# badge2.net
KiCad netlist of a schematic drawn in EAGLE
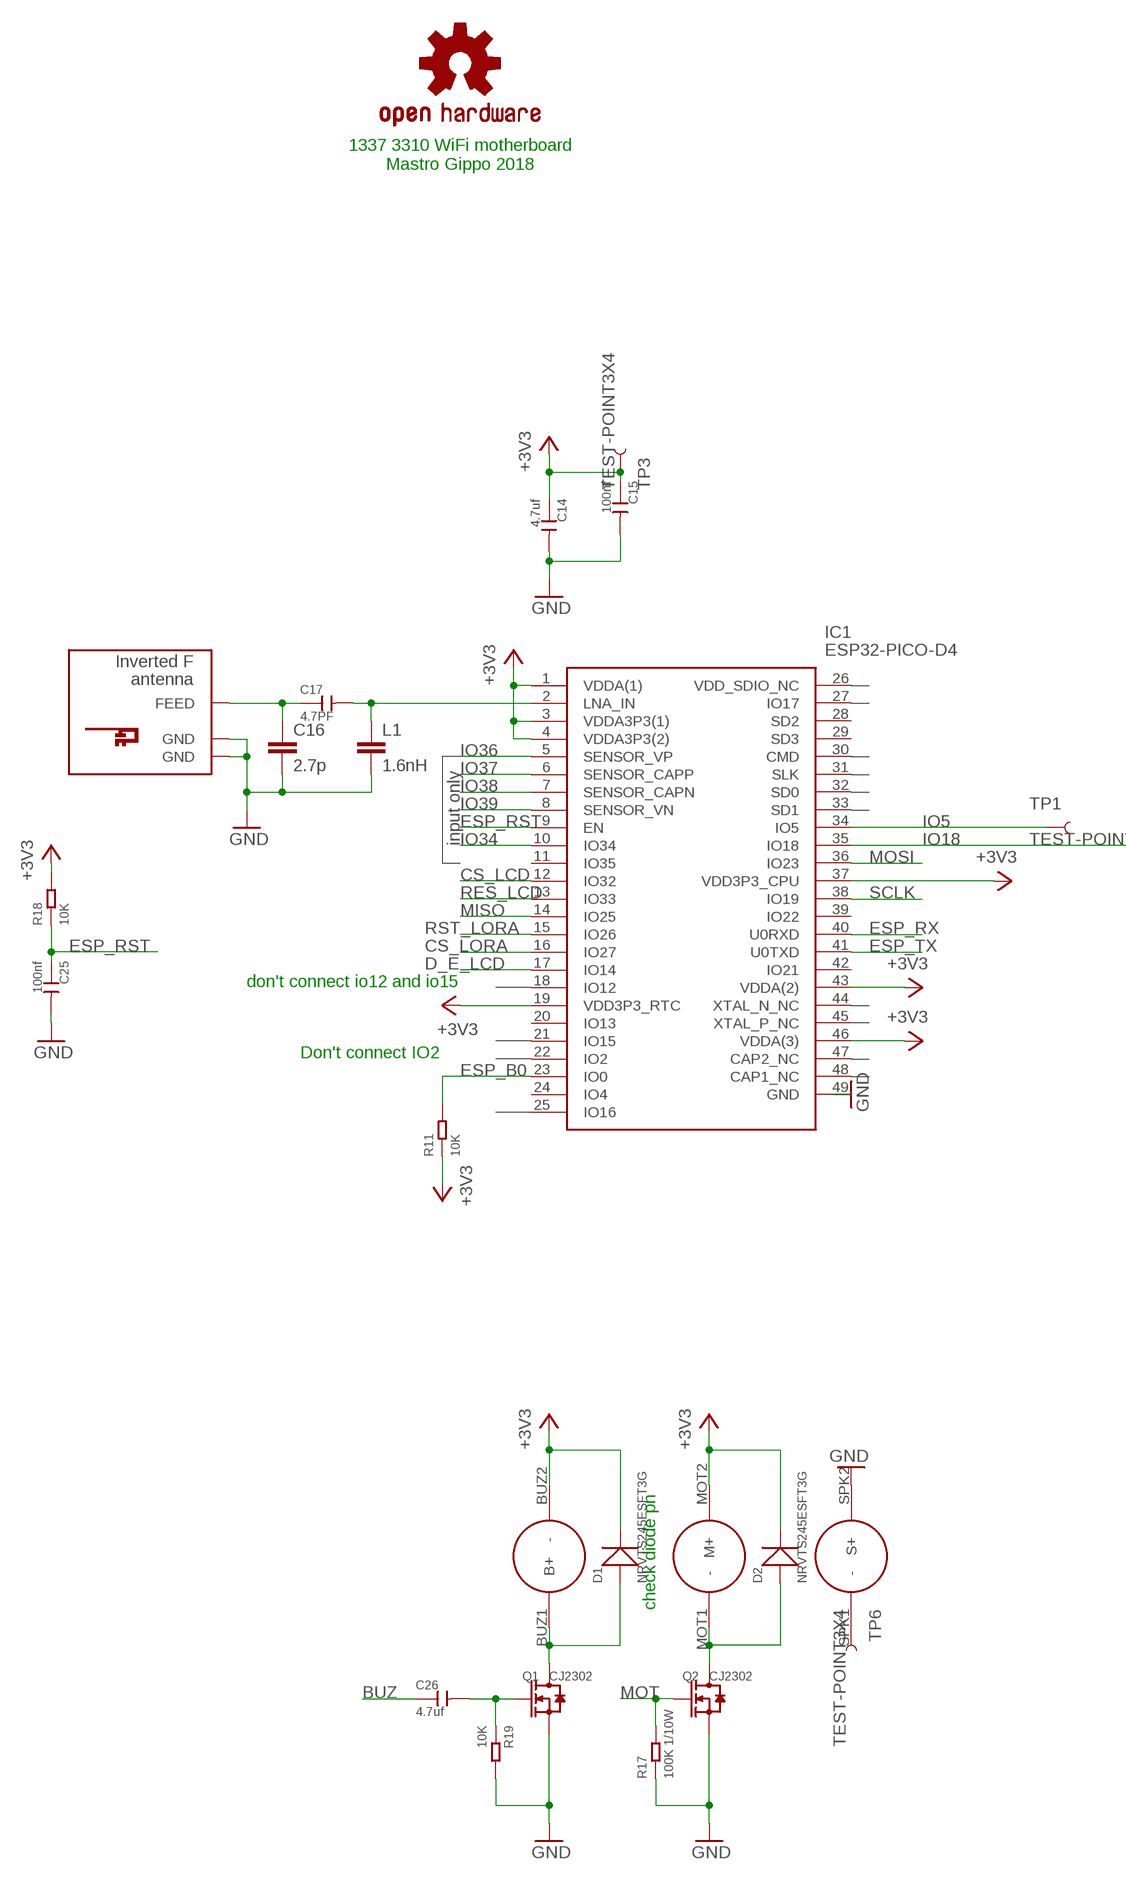
[diagram p0: schematic, sheet 1, part 1 of 2]
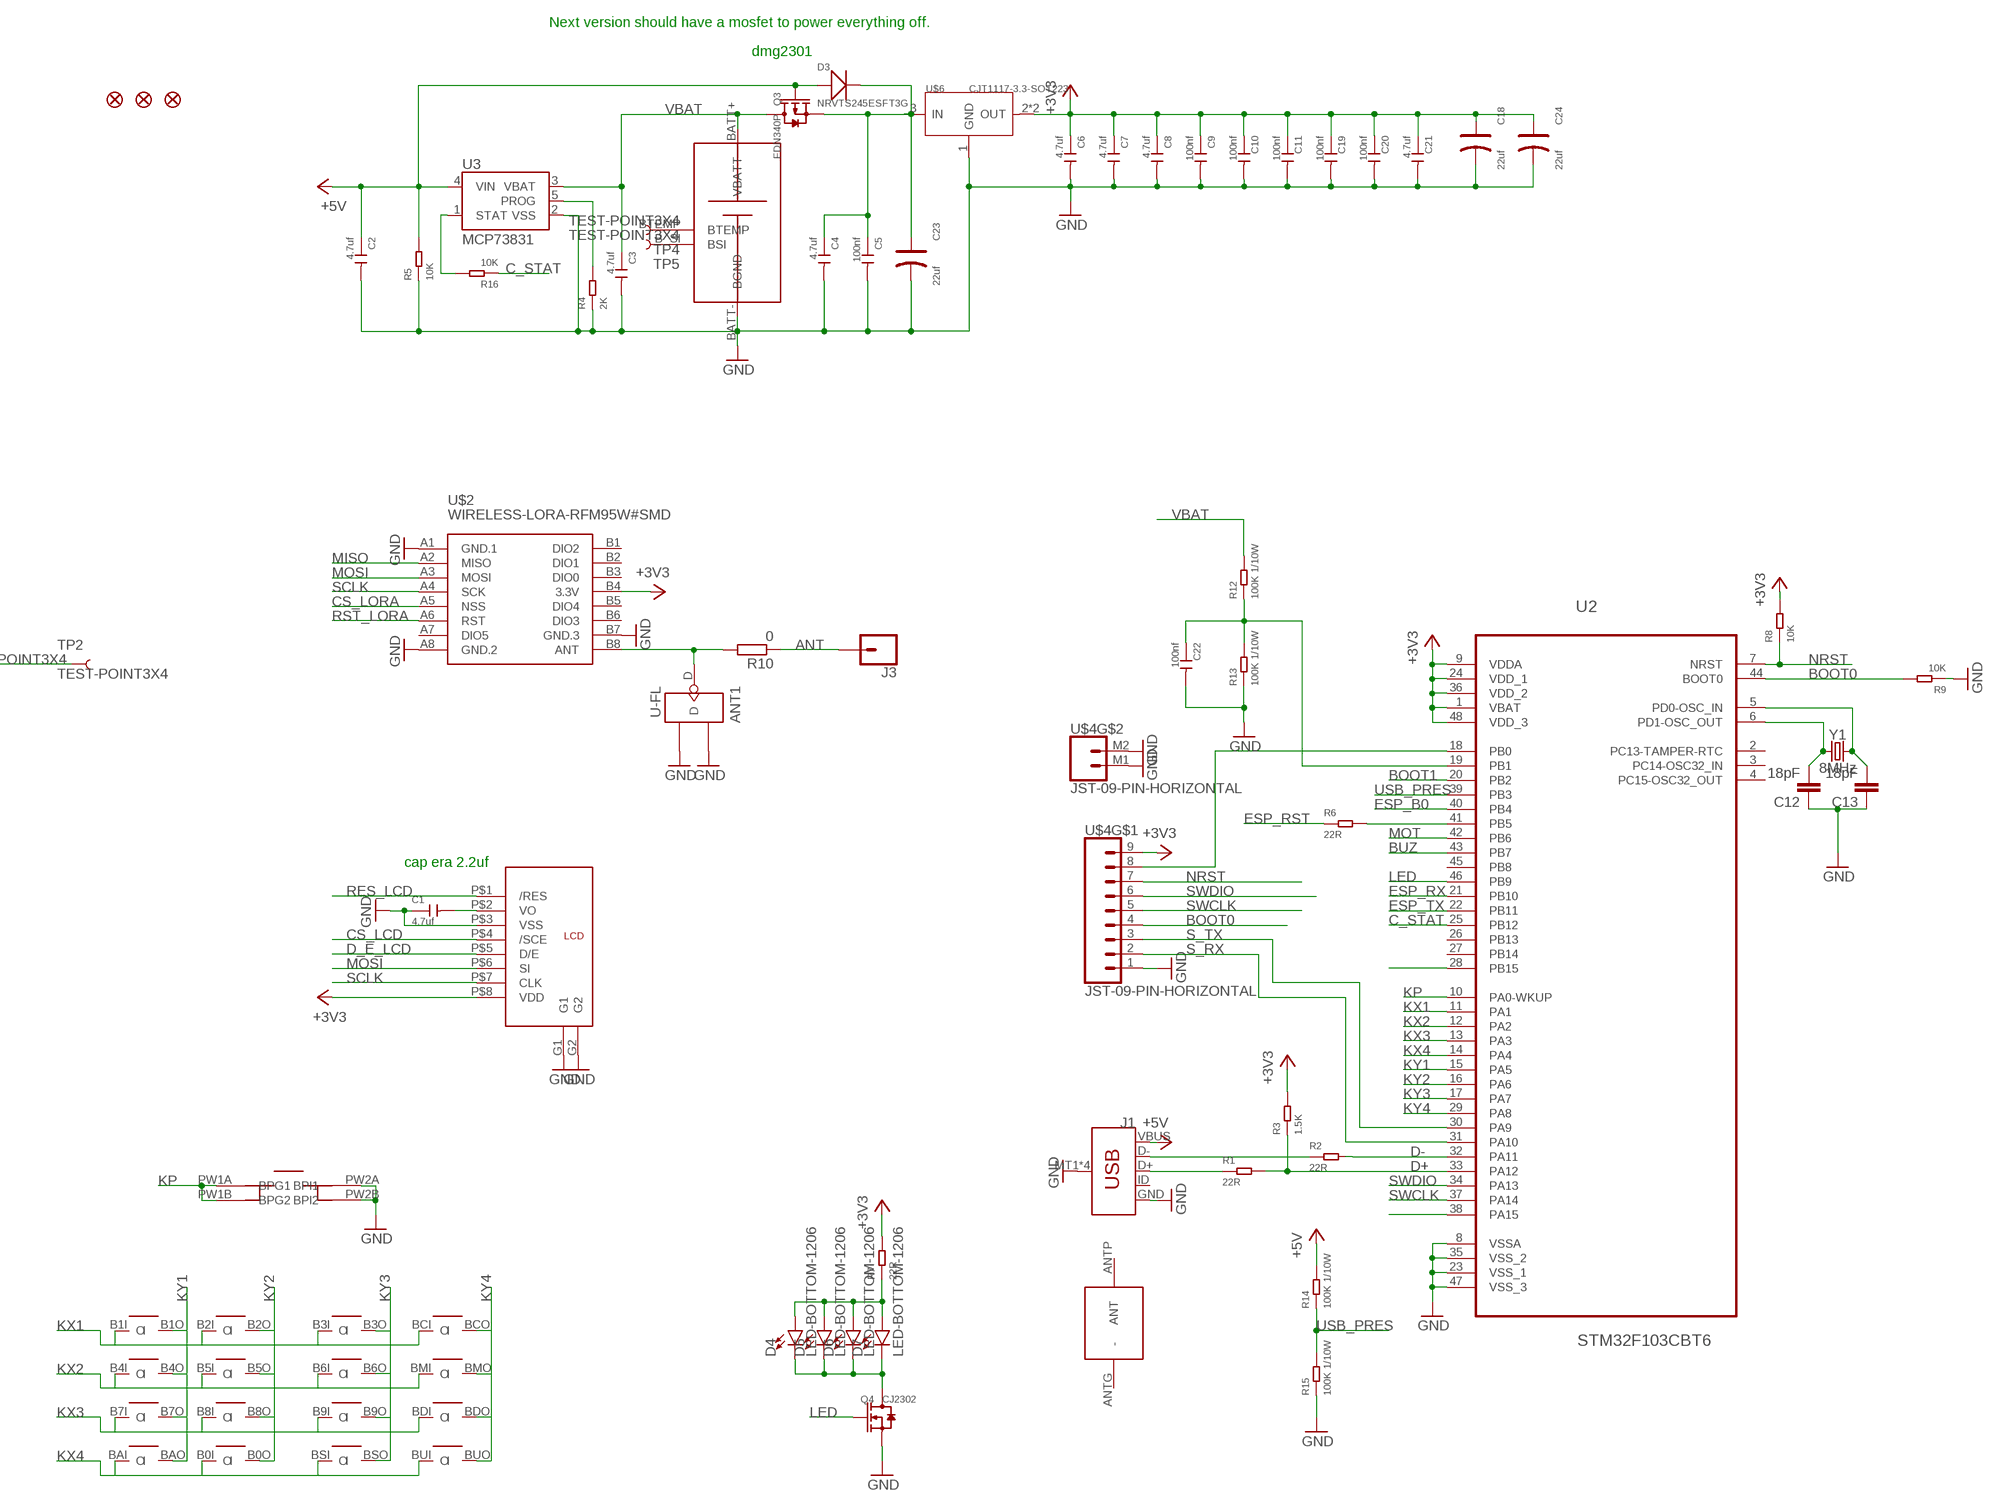
[diagram p1: schematic, sheet 1, part 2 of 2]

(export (version "E")
  (design (tool "Eeschema 10.0.6"))
  (components
    (comp (ref "ANT1")
      (value "U-FL")
      (footprint "eagle-import:U-FL3P-SMD-2.6X2.6X1.0MM")
      (libsource (lib "eagle-import") (part "ANTENNA-CONN-U-FL(3P)"))
    )
    (comp (ref "C1")
      (value "4.7uf")
      (footprint "eagle-import:C0603")
      (fields (field (name "MPN") "CC0603KRX5R6BB475"))
      (libsource (lib "eagle-import") (part "CERAMIC-4.7UF-10V-10%-X5R(0603)"))
    )
    (comp (ref "C2")
      (value "4.7uf")
      (footprint "eagle-import:C0603")
      (fields (field (name "MPN") "CC0603KRX5R6BB475"))
      (libsource (lib "eagle-import") (part "CERAMIC-4.7UF-10V-10%-X5R(0603)"))
    )
    (comp (ref "C3")
      (value "4.7uf")
      (footprint "eagle-import:C0603")
      (fields (field (name "MPN") "CC0603KRX5R6BB475"))
      (libsource (lib "eagle-import") (part "CERAMIC-4.7UF-10V-10%-X5R(0603)"))
    )
    (comp (ref "C4")
      (value "4.7uf")
      (footprint "eagle-import:C0603")
      (fields (field (name "MPN") "CC0603KRX5R6BB475"))
      (libsource (lib "eagle-import") (part "CERAMIC-4.7UF-10V-10%-X5R(0603)"))
    )
    (comp (ref "C5")
      (value "100nf")
      (footprint "eagle-import:C0603")
      (fields (field (name "MPN") "CC0603KRX7R9BB104"))
      (libsource (lib "eagle-import") (part "CERAMIC-100NF-50V-10%-X7R(0603)"))
    )
    (comp (ref "C6")
      (value "4.7uf")
      (footprint "eagle-import:C0603")
      (fields (field (name "MPN") "CC0603KRX5R6BB475"))
      (libsource (lib "eagle-import") (part "CERAMIC-4.7UF-10V-10%-X5R(0603)"))
    )
    (comp (ref "C7")
      (value "4.7uf")
      (footprint "eagle-import:C0603")
      (fields (field (name "MPN") "CC0603KRX5R6BB475"))
      (libsource (lib "eagle-import") (part "CERAMIC-4.7UF-10V-10%-X5R(0603)"))
    )
    (comp (ref "C8")
      (value "4.7uf")
      (footprint "eagle-import:C0603")
      (fields (field (name "MPN") "CC0603KRX5R6BB475"))
      (libsource (lib "eagle-import") (part "CERAMIC-4.7UF-10V-10%-X5R(0603)"))
    )
    (comp (ref "C9")
      (value "100nf")
      (footprint "eagle-import:C0603")
      (fields (field (name "MPN") "CC0603KRX7R9BB104"))
      (libsource (lib "eagle-import") (part "CERAMIC-100NF-50V-10%-X7R(0603)"))
    )
    (comp (ref "C10")
      (value "100nf")
      (footprint "eagle-import:C0603")
      (fields (field (name "MPN") "CC0603KRX7R9BB104"))
      (libsource (lib "eagle-import") (part "CERAMIC-100NF-50V-10%-X7R(0603)"))
    )
    (comp (ref "C11")
      (value "100nf")
      (footprint "eagle-import:C0603")
      (fields (field (name "MPN") "CC0603KRX7R9BB104"))
      (libsource (lib "eagle-import") (part "CERAMIC-100NF-50V-10%-X7R(0603)"))
    )
    (comp (ref "C12")
      (value "18pF")
      (footprint "eagle-import:0603")
      (libsource (lib "eagle-import") (part "18PF-0603-50V-5%"))
    )
    (comp (ref "C13")
      (value "18pF")
      (footprint "eagle-import:0603")
      (libsource (lib "eagle-import") (part "18PF-0603-50V-5%"))
    )
    (comp (ref "C14")
      (value "4.7uf")
      (footprint "eagle-import:C0603")
      (fields (field (name "MPN") "CC0603KRX5R6BB475"))
      (libsource (lib "eagle-import") (part "CERAMIC-4.7UF-10V-10%-X5R(0603)"))
    )
    (comp (ref "C15")
      (value "100nf")
      (footprint "eagle-import:C0603")
      (fields (field (name "MPN") "CC0603KRX7R9BB104"))
      (libsource (lib "eagle-import") (part "CERAMIC-100NF-50V-10%-X7R(0603)"))
    )
    (comp (ref "C16")
      (value "2.7p")
      (footprint "eagle-import:C0603")
      (libsource (lib "eagle-import") (part "C-EUC0603"))
    )
    (comp (ref "C17")
      (value "4.7PF")
      (footprint "eagle-import:C0603")
      (fields (field (name "MPN") "CC0603CRNPO9BN4R7"))
      (libsource (lib "eagle-import") (part "CERAMIC-4.7PF-50V-0.25PF-NPO(0603)"))
    )
    (comp (ref "C18")
      (value "22uf")
      (footprint "eagle-import:AVX-B")
      (fields (field (name "MPN") "TAJB226*016#NJ"))
      (libsource (lib "eagle-import") (part "TANTALUM-SMD-22UF-16V(AVX-B)"))
    )
    (comp (ref "C19")
      (value "100nf")
      (footprint "eagle-import:C0603")
      (fields (field (name "MPN") "CC0603KRX7R9BB104"))
      (libsource (lib "eagle-import") (part "CERAMIC-100NF-50V-10%-X7R(0603)"))
    )
    (comp (ref "C20")
      (value "100nf")
      (footprint "eagle-import:C0603")
      (fields (field (name "MPN") "CC0603KRX7R9BB104"))
      (libsource (lib "eagle-import") (part "CERAMIC-100NF-50V-10%-X7R(0603)"))
    )
    (comp (ref "C21")
      (value "4.7uf")
      (footprint "eagle-import:C0603")
      (fields (field (name "MPN") "CC0603KRX5R6BB475"))
      (libsource (lib "eagle-import") (part "CERAMIC-4.7UF-10V-10%-X5R(0603)"))
    )
    (comp (ref "C22")
      (value "100nf")
      (footprint "eagle-import:C0603")
      (fields (field (name "MPN") "CC0603KRX7R9BB104"))
      (libsource (lib "eagle-import") (part "CERAMIC-100NF-50V-10%-X7R(0603)"))
    )
    (comp (ref "C23")
      (value "22uf")
      (footprint "eagle-import:AVX-B")
      (fields (field (name "MPN") "TAJB226*016#NJ"))
      (libsource (lib "eagle-import") (part "TANTALUM-SMD-22UF-16V(AVX-B)"))
    )
    (comp (ref "C24")
      (value "22uf")
      (footprint "eagle-import:AVX-B")
      (fields (field (name "MPN") "TAJB226*016#NJ"))
      (libsource (lib "eagle-import") (part "TANTALUM-SMD-22UF-16V(AVX-B)"))
    )
    (comp (ref "C25")
      (value "100nf")
      (footprint "eagle-import:C0603")
      (fields (field (name "MPN") "CC0603KRX7R9BB104"))
      (libsource (lib "eagle-import") (part "CERAMIC-100NF-50V-10%-X7R(0603)"))
    )
    (comp (ref "C26")
      (value "4.7uf")
      (footprint "eagle-import:C0603")
      (fields (field (name "MPN") "CC0603KRX5R6BB475"))
      (libsource (lib "eagle-import") (part "CERAMIC-4.7UF-10V-10%-X5R(0603)"))
    )
    (comp (ref "D1")
      (value "NRVTS245ESFT3G")
      (footprint "eagle-import:SOD-123")
      (fields (field (name "MPN") "B5819W"))
      (libsource (lib "eagle-import") (part "SMD-DIODE-SCHOTTKY-20V-1A(SOD-123)"))
    )
    (comp (ref "D2")
      (value "NRVTS245ESFT3G")
      (footprint "eagle-import:SOD-123")
      (fields (field (name "MPN") "B5819W"))
      (libsource (lib "eagle-import") (part "SMD-DIODE-SCHOTTKY-20V-1A(SOD-123)"))
    )
    (comp (ref "D3")
      (value "NRVTS245ESFT3G")
      (footprint "eagle-import:SOD-123")
      (fields (field (name "MPN") "B5819W"))
      (libsource (lib "eagle-import") (part "SMD-DIODE-SCHOTTKY-20V-1A(SOD-123)"))
    )
    (comp (ref "D4")
      (value "LED-BOTTOM-1206")
      (footprint "eagle-import:LED-1206")
      (libsource (lib "eagle-import") (part "LED-BOTTOM-1206"))
    )
    (comp (ref "D5")
      (value "LED-BOTTOM-1206")
      (footprint "eagle-import:LED-1206")
      (libsource (lib "eagle-import") (part "LED-BOTTOM-1206"))
    )
    (comp (ref "D6")
      (value "LED-BOTTOM-1206")
      (footprint "eagle-import:LED-1206")
      (libsource (lib "eagle-import") (part "LED-BOTTOM-1206"))
    )
    (comp (ref "D7")
      (value "LED-BOTTOM-1206")
      (footprint "eagle-import:LED-1206")
      (libsource (lib "eagle-import") (part "LED-BOTTOM-1206"))
    )
    (comp (ref "FID1")
      (value "FIDUCIAL1.5X3")
      (footprint "eagle-import:FIDUCIAL-1.5X3")
      (libsource (lib "eagle-import") (part "FIDUCIAL1.5X3"))
    )
    (comp (ref "FID2")
      (value "FIDUCIAL1.5X3")
      (footprint "eagle-import:FIDUCIAL-1.5X3")
      (libsource (lib "eagle-import") (part "FIDUCIAL1.5X3"))
    )
    (comp (ref "FID3")
      (value "FIDUCIAL1.5X3")
      (footprint "eagle-import:FIDUCIAL-1.5X3")
      (libsource (lib "eagle-import") (part "FIDUCIAL1.5X3"))
    )
    (comp (ref "IC1")
      (value "ESP32-PICO-D4")
      (footprint "eagle-import:ESP32-PICO-D4_1")
      (libsource (lib "eagle-import") (part "ESP32-PICO-D4"))
    )
    (comp (ref "J1")
      (value "USB_MICRO-B_SMT")
      (footprint "eagle-import:USB-MICROB")
      (libsource (lib "eagle-import") (part "USB_MICRO-B_SMT"))
    )
    (comp (ref "J3")
      (value "CONN_01POGOPIN_HOLE_0.58")
      (footprint "eagle-import:1X01_POGOPIN_HOLE_0.58_DIA")
      (libsource (lib "eagle-import") (part "CONN_01POGOPIN_HOLE_0.58"))
    )
    (comp (ref "L1")
      (value "1.6nH")
      (footprint "eagle-import:C0603K")
      (libsource (lib "eagle-import") (part "C-EUC0603K"))
    )
    (comp (ref "LOGO1")
      (value "OSHW-LOGOM")
      (footprint "eagle-import:OSHW-LOGO-M")
      (libsource (lib "eagle-import") (part "OSHW-LOGOM"))
    )
    (comp (ref "Q1")
      (value "CJ2302")
      (footprint "eagle-import:SOT-23")
      (libsource (lib "eagle-import") (part "Seeed-Transistor_477_SMD-MOSFET-N-CH-20V-2.1A-CJ2302(SOT-23)"))
    )
    (comp (ref "Q2")
      (value "CJ2302")
      (footprint "eagle-import:SOT-23")
      (libsource (lib "eagle-import") (part "SMD-MOSFET-N-CH-20V-2.1A-CJ2302(SOT-23)"))
    )
    (comp (ref "Q3")
      (value "FDN340P")
      (footprint "eagle-import:SOT-23")
      (libsource (lib "eagle-import") (part "SMD-MOSFET-P-CH-20V-2A-FDN340P(SOT-23)"))
    )
    (comp (ref "Q4")
      (value "CJ2302")
      (footprint "eagle-import:SOT-23")
      (libsource (lib "eagle-import") (part "Seeed-Transistor_477_SMD-MOSFET-N-CH-20V-2.1A-CJ2302(SOT-23)"))
    )
    (comp (ref "R1")
      (value "22R")
      (footprint "eagle-import:R0603")
      (fields (field (name "MPN") "RC0603JR-0722RL"))
      (libsource (lib "eagle-import") (part "SMD-RES-22R-5%-1/10W(0603)"))
    )
    (comp (ref "R2")
      (value "22R")
      (footprint "eagle-import:R0603")
      (fields (field (name "MPN") "RC0603JR-0722RL"))
      (libsource (lib "eagle-import") (part "SMD-RES-22R-5%-1/10W(0603)"))
    )
    (comp (ref "R3")
      (value "1.5K")
      (footprint "eagle-import:R0603")
      (fields (field (name "MPN") "RC0603FR-071K5L"))
      (libsource (lib "eagle-import") (part "SMD-RES-1.5K-1%-1/10W(0603)"))
    )
    (comp (ref "R4")
      (value "2K")
      (footprint "eagle-import:R0603")
      (fields (field (name "MPN") "RC0603FR-072KL"))
      (libsource (lib "eagle-import") (part "SMD-RES-2K-1%-1/10W(0603)"))
    )
    (comp (ref "R5")
      (value "10K")
      (footprint "eagle-import:R0603")
      (fields (field (name "MPN") "RC0603FR-0710KL"))
      (libsource (lib "eagle-import") (part "SMD-RES-10K-1%-1/10W(0603)"))
    )
    (comp (ref "R6")
      (value "22R")
      (footprint "eagle-import:R0603")
      (fields (field (name "MPN") "RC0603JR-0722RL"))
      (libsource (lib "eagle-import") (part "SMD-RES-22R-5%-1/10W(0603)"))
    )
    (comp (ref "R7")
      (value "22R")
      (footprint "eagle-import:R0603")
      (fields (field (name "MPN") "RC0603JR-0722RL"))
      (libsource (lib "eagle-import") (part "SMD-RES-22R-5%-1/10W(0603)"))
    )
    (comp (ref "R8")
      (value "10K")
      (footprint "eagle-import:R0603")
      (fields (field (name "MPN") "RC0603FR-0710KL"))
      (libsource (lib "eagle-import") (part "SMD-RES-10K-1%-1/10W(0603)"))
    )
    (comp (ref "R9")
      (value "10K")
      (footprint "eagle-import:R0603")
      (fields (field (name "MPN") "RC0603FR-0710KL"))
      (libsource (lib "eagle-import") (part "SMD-RES-10K-1%-1/10W(0603)"))
    )
    (comp (ref "R10")
      (value "0")
      (footprint "eagle-import:R0603")
      (libsource (lib "eagle-import") (part "R-EU_R0603"))
    )
    (comp (ref "R11")
      (value "10K")
      (footprint "eagle-import:R0603")
      (fields (field (name "MPN") "RC0603FR-0710KL"))
      (libsource (lib "eagle-import") (part "SMD-RES-10K-1%-1/10W(0603)"))
    )
    (comp (ref "R12")
      (value "100K 1/10W")
      (footprint "eagle-import:R0603")
      (fields (field (name "MPN") "RC0603JR-07100KL"))
      (libsource (lib "eagle-import") (part "SMD-RES-100K-5%-1/10W(0603)"))
    )
    (comp (ref "R13")
      (value "100K 1/10W")
      (footprint "eagle-import:R0603")
      (fields (field (name "MPN") "RC0603JR-07100KL"))
      (libsource (lib "eagle-import") (part "SMD-RES-100K-5%-1/10W(0603)"))
    )
    (comp (ref "R14")
      (value "100K 1/10W")
      (footprint "eagle-import:R0603")
      (fields (field (name "MPN") "RC0603JR-07100KL"))
      (libsource (lib "eagle-import") (part "SMD-RES-100K-5%-1/10W(0603)"))
    )
    (comp (ref "R15")
      (value "100K 1/10W")
      (footprint "eagle-import:R0603")
      (fields (field (name "MPN") "RC0603JR-07100KL"))
      (libsource (lib "eagle-import") (part "SMD-RES-100K-5%-1/10W(0603)"))
    )
    (comp (ref "R16")
      (value "10K")
      (footprint "eagle-import:R0603")
      (fields (field (name "MPN") "RC0603FR-0710KL"))
      (libsource (lib "eagle-import") (part "SMD-RES-10K-1%-1/10W(0603)"))
    )
    (comp (ref "R17")
      (value "100K 1/10W")
      (footprint "eagle-import:R0603")
      (fields (field (name "MPN") "RC0603JR-07100KL"))
      (libsource (lib "eagle-import") (part "SMD-RES-100K-5%-1/10W(0603)"))
    )
    (comp (ref "R18")
      (value "10K")
      (footprint "eagle-import:R0603")
      (fields (field (name "MPN") "RC0603FR-0710KL"))
      (libsource (lib "eagle-import") (part "SMD-RES-10K-1%-1/10W(0603)"))
    )
    (comp (ref "R19")
      (value "10K")
      (footprint "eagle-import:R0603")
      (fields (field (name "MPN") "RC0603FR-0710KL"))
      (libsource (lib "eagle-import") (part "SMD-RES-10K-1%-1/10W(0603)"))
    )
    (comp (ref "TP1")
      (value "TEST-POINT3X4")
      (footprint "eagle-import:PAD.03X.04")
      (libsource (lib "eagle-import") (part "TEST-POINT3X4"))
    )
    (comp (ref "TP2")
      (value "TEST-POINT3X4")
      (footprint "eagle-import:PAD.03X.04")
      (libsource (lib "eagle-import") (part "TEST-POINT3X4"))
    )
    (comp (ref "TP3")
      (value "TEST-POINT3X4")
      (footprint "eagle-import:PAD.03X.04")
      (libsource (lib "eagle-import") (part "TEST-POINT3X4"))
    )
    (comp (ref "TP4")
      (value "TEST-POINT3X4")
      (footprint "eagle-import:PAD.03X.04")
      (libsource (lib "eagle-import") (part "TEST-POINT3X4"))
    )
    (comp (ref "TP5")
      (value "TEST-POINT3X4")
      (footprint "eagle-import:PAD.03X.04")
      (libsource (lib "eagle-import") (part "TEST-POINT3X4"))
    )
    (comp (ref "TP6")
      (value "TEST-POINT3X4")
      (footprint "eagle-import:PAD.03X.04")
      (libsource (lib "eagle-import") (part "TEST-POINT3X4"))
    )
    (comp (ref "U$1")
      (value "3310PANEL")
      (footprint "eagle-import:3310LCD")
      (libsource (lib "eagle-import") (part "3310PANEL"))
    )
    (comp (ref "U$2")
      (value "WIRELESS-LORA-RFM95W#SMD")
      (footprint "eagle-import:WIRELESS-LORA-RFM95W#SMD")
      (libsource (lib "eagle-import") (part "WIRELESS-LORA-RFM95W#SMD"))
    )
    (comp (ref "U$3")
      (value "INVERTED_F_ANTENNA+2")
      (footprint "eagle-import:DN007+2")
      (libsource (lib "eagle-import") (part "INVERTED_F_ANTENNA+2"))
    )
    (comp (ref "U$4")
      (value "JST-09-PIN-HORIZONTAL")
      (footprint "eagle-import:JST-09-SMD-HORI-1.0MM")
      (libsource (lib "eagle-import") (part "JST-09-PIN-HORIZONTAL"))
    )
    (comp (ref "U$6")
      (value "CJT1117-3.3-SOT223")
      (footprint "eagle-import:SOT-223")
      (fields (field (name "MPN") "CJT1117-3.3"))
      (libsource (lib "eagle-import") (part "PMIC-CJT1117-3.3(SOT223)"))
    )
    (comp (ref "U2")
      (value "STM32F103CBT6")
      (footprint "eagle-import:QFP50P900X900X160-48N")
      (libsource (lib "eagle-import") (part "STM32F103CBT6"))
    )
    (comp (ref "U3")
      (value "MCP73831")
      (footprint "eagle-import:SOT23-5")
      (libsource (lib "eagle-import") (part "MCP73831"))
    )
    (comp (ref "Y1")
      (value "8MHz")
      (footprint "eagle-import:CRYSTAL-SMD-5X3.2-4PAD")
      (libsource (lib "eagle-import") (part "CRYSTAL-8MHZSMD-5X3.2"))
    )
  )
  (nets
    (net (code "1") (name "+3V3") (class "Default")
      (node (ref "C10") (pin "1") (pinfunction "1_1") (pintype "passive"))
      (node (ref "C11") (pin "1") (pinfunction "1_1") (pintype "passive"))
      (node (ref "C14") (pin "1") (pinfunction "1_1") (pintype "passive"))
      (node (ref "C15") (pin "1") (pinfunction "1_1") (pintype "passive"))
      (node (ref "C18") (pin "+") (pinfunction "+_+") (pintype "passive"))
      (node (ref "C19") (pin "1") (pinfunction "1_1") (pintype "passive"))
      (node (ref "C20") (pin "1") (pinfunction "1_1") (pintype "passive"))
      (node (ref "C21") (pin "1") (pinfunction "1_1") (pintype "passive"))
      (node (ref "C24") (pin "+") (pinfunction "+_+") (pintype "passive"))
      (node (ref "C6") (pin "1") (pinfunction "1_1") (pintype "passive"))
      (node (ref "C7") (pin "1") (pinfunction "1_1") (pintype "passive"))
      (node (ref "C8") (pin "1") (pinfunction "1_1") (pintype "passive"))
      (node (ref "C9") (pin "1") (pinfunction "1_1") (pintype "passive"))
      (node (ref "D1") (pin "-") (pinfunction "-_-") (pintype "passive"))
      (node (ref "D2") (pin "-") (pinfunction "-_-") (pintype "passive"))
      (node (ref "IC1") (pin "1") (pinfunction "VDDA(1)_1") (pintype "bidirectional"))
      (node (ref "IC1") (pin "19") (pinfunction "VDD3P3_RTC_19") (pintype "bidirectional"))
      (node (ref "IC1") (pin "3") (pinfunction "VDDA3P3(1)_3") (pintype "bidirectional"))
      (node (ref "IC1") (pin "37") (pinfunction "VDD3P3_CPU_37") (pintype "bidirectional"))
      (node (ref "IC1") (pin "4") (pinfunction "VDDA3P3(2)_4") (pintype "bidirectional"))
      (node (ref "IC1") (pin "43") (pinfunction "VDDA(2)_43") (pintype "bidirectional"))
      (node (ref "IC1") (pin "46") (pinfunction "VDDA(3)_46") (pintype "bidirectional"))
      (node (ref "R11") (pin "1") (pinfunction "1_1") (pintype "passive"))
      (node (ref "R18") (pin "2") (pinfunction "2_2") (pintype "passive"))
      (node (ref "R3") (pin "2") (pinfunction "2_2") (pintype "passive"))
      (node (ref "R7") (pin "2") (pinfunction "2_2") (pintype "passive"))
      (node (ref "R8") (pin "2") (pinfunction "2_2") (pintype "passive"))
      (node (ref "TP3") (pin "P$1") (pinfunction "1_P$1") (pintype "bidirectional"))
      (node (ref "U$1") (pin "BUZ2") (pinfunction "-_BUZ2") (pintype "bidirectional"))
      (node (ref "U$1") (pin "MOT2") (pinfunction "M+_MOT2") (pintype "bidirectional"))
      (node (ref "U$1") (pin "P$8") (pinfunction "VDD_P$8") (pintype "bidirectional"))
      (node (ref "U$2") (pin "B4") (pinfunction "3.3V_B4") (pintype "power_in"))
      (node (ref "U$4") (pin "9") (pinfunction "9_9") (pintype "passive"))
      (node (ref "U$6") (pin "2") (pinfunction "OUT_2") (pintype "bidirectional"))
      (node (ref "U$6") (pin "TER") (pinfunction "OUT_TER") (pintype "bidirectional"))
      (node (ref "U2") (pin "1") (pinfunction "VBAT_1") (pintype "input"))
      (node (ref "U2") (pin "24") (pinfunction "VDD_1_24") (pintype "bidirectional"))
      (node (ref "U2") (pin "36") (pinfunction "VDD_2_36") (pintype "power_in"))
      (node (ref "U2") (pin "48") (pinfunction "VDD_3_48") (pintype "power_in"))
      (node (ref "U2") (pin "9") (pinfunction "VDDA_9") (pintype "power_in"))
    )
    (net (code "2") (name "+5V") (class "Default")
      (node (ref "C2") (pin "1") (pinfunction "1_1") (pintype "passive"))
      (node (ref "D3") (pin "+") (pinfunction "+_+") (pintype "passive"))
      (node (ref "J1") (pin "VBUS") (pinfunction "VBUS_VBUS") (pintype "power_in"))
      (node (ref "Q3") (pin "1") (pinfunction "G_1") (pintype "passive"))
      (node (ref "R14") (pin "2") (pinfunction "2_2") (pintype "passive"))
      (node (ref "R5") (pin "2") (pinfunction "2_2") (pintype "passive"))
      (node (ref "U3") (pin "4") (pinfunction "VIN_4") (pintype "power_in"))
    )
    (net (code "3") (name "/ANT") (class "Default")
      (node (ref "J3") (pin "1") (pinfunction "1_1") (pintype "passive"))
      (node (ref "R10") (pin "1") (pinfunction "1_1") (pintype "passive"))
    )
    (net (code "4") (name "/BOOT0") (class "Default")
      (node (ref "R9") (pin "2") (pinfunction "2_2") (pintype "passive"))
      (node (ref "U$4") (pin "4") (pinfunction "4_4") (pintype "passive"))
      (node (ref "U2") (pin "44") (pinfunction "BOOT0_44") (pintype "bidirectional"))
    )
    (net (code "5") (name "/BOOT1") (class "Default")
      (node (ref "U2") (pin "20") (pinfunction "PB2_20") (pintype "bidirectional"))
    )
    (net (code "6") (name "/BUZ") (class "Default")
      (node (ref "C26") (pin "1") (pinfunction "1_1") (pintype "passive"))
      (node (ref "U2") (pin "43") (pinfunction "PB7_43") (pintype "bidirectional"))
    )
    (net (code "7") (name "/CS_LCD") (class "Default")
      (node (ref "IC1") (pin "12") (pinfunction "IO32_12") (pintype "bidirectional"))
      (node (ref "U$1") (pin "P$4") (pinfunction "/SCE_P$4") (pintype "bidirectional"))
    )
    (net (code "8") (name "/CS_LORA") (class "Default")
      (node (ref "IC1") (pin "16") (pinfunction "IO27_16") (pintype "bidirectional"))
      (node (ref "U$2") (pin "A5") (pinfunction "NSS_A5") (pintype "bidirectional"))
    )
    (net (code "9") (name "/C_STAT") (class "Default")
      (node (ref "R16") (pin "1") (pinfunction "1_1") (pintype "passive"))
      (node (ref "U2") (pin "25") (pinfunction "PB12_25") (pintype "bidirectional"))
    )
    (net (code "10") (name "/D+") (class "Default")
      (node (ref "R1") (pin "2") (pinfunction "2_2") (pintype "passive"))
      (node (ref "R3") (pin "1") (pinfunction "1_1") (pintype "passive"))
      (node (ref "U2") (pin "33") (pinfunction "PA12_33") (pintype "bidirectional"))
    )
    (net (code "11") (name "/D-") (class "Default")
      (node (ref "R2") (pin "2") (pinfunction "2_2") (pintype "passive"))
      (node (ref "U2") (pin "32") (pinfunction "PA11_32") (pintype "power_in"))
    )
    (net (code "12") (name "/D_E_LCD") (class "Default")
      (node (ref "IC1") (pin "17") (pinfunction "IO14_17") (pintype "bidirectional"))
      (node (ref "U$1") (pin "P$5") (pinfunction "D/E_P$5") (pintype "bidirectional"))
    )
    (net (code "13") (name "/ESP_B0") (class "Default")
      (node (ref "IC1") (pin "23") (pinfunction "IO0_23") (pintype "bidirectional"))
      (node (ref "R11") (pin "2") (pinfunction "2_2") (pintype "passive"))
      (node (ref "U2") (pin "40") (pinfunction "PB4_40") (pintype "bidirectional"))
    )
    (net (code "14") (name "/ESP_RST") (class "Default")
      (node (ref "C25") (pin "1") (pinfunction "1_1") (pintype "passive"))
      (node (ref "IC1") (pin "9") (pinfunction "EN_9") (pintype "bidirectional"))
      (node (ref "R18") (pin "1") (pinfunction "1_1") (pintype "passive"))
      (node (ref "R6") (pin "1") (pinfunction "1_1") (pintype "passive"))
    )
    (net (code "15") (name "/ESP_RX") (class "Default")
      (node (ref "IC1") (pin "40") (pinfunction "U0RXD_40") (pintype "bidirectional"))
      (node (ref "U2") (pin "21") (pinfunction "PB10_21") (pintype "bidirectional"))
    )
    (net (code "16") (name "/ESP_TX") (class "Default")
      (node (ref "IC1") (pin "41") (pinfunction "U0TXD_41") (pintype "bidirectional"))
      (node (ref "U2") (pin "22") (pinfunction "PB11_22") (pintype "bidirectional"))
    )
    (net (code "17") (name "/IO5") (class "Default")
      (node (ref "IC1") (pin "34") (pinfunction "IO5_34") (pintype "bidirectional"))
      (node (ref "TP1") (pin "P$1") (pinfunction "1_P$1") (pintype "bidirectional"))
    )
    (net (code "18") (name "/IO18") (class "Default")
      (node (ref "IC1") (pin "35") (pinfunction "IO18_35") (pintype "bidirectional"))
      (node (ref "TP2") (pin "P$1") (pinfunction "1_P$1") (pintype "bidirectional"))
    )
    (net (code "19") (name "/IO34") (class "Default")
      (node (ref "IC1") (pin "10") (pinfunction "IO34_10") (pintype "bidirectional"))
    )
    (net (code "20") (name "/IO36") (class "Default")
      (node (ref "IC1") (pin "5") (pinfunction "SENSOR_VP_5") (pintype "bidirectional"))
    )
    (net (code "21") (name "/IO37") (class "Default")
      (node (ref "IC1") (pin "6") (pinfunction "SENSOR_CAPP_6") (pintype "bidirectional"))
    )
    (net (code "22") (name "/IO38") (class "Default")
      (node (ref "IC1") (pin "7") (pinfunction "SENSOR_CAPN_7") (pintype "bidirectional"))
    )
    (net (code "23") (name "/IO39") (class "Default")
      (node (ref "IC1") (pin "8") (pinfunction "SENSOR_VN_8") (pintype "bidirectional"))
    )
    (net (code "24") (name "/KP") (class "Default")
      (node (ref "U$1") (pin "PW1A") (pinfunction "BPG1_PW1A") (pintype "bidirectional"))
      (node (ref "U$1") (pin "PW1B") (pinfunction "BPG2_PW1B") (pintype "bidirectional"))
      (node (ref "U2") (pin "10") (pinfunction "PA0-WKUP_10") (pintype "bidirectional"))
    )
    (net (code "25") (name "/KX1") (class "Default")
      (node (ref "U$1") (pin "B1I") (pinfunction "I_B1I") (pintype "bidirectional"))
      (node (ref "U$1") (pin "B2I") (pinfunction "I_B2I") (pintype "bidirectional"))
      (node (ref "U$1") (pin "B3I") (pinfunction "I_B3I") (pintype "bidirectional"))
      (node (ref "U$1") (pin "BCI") (pinfunction "I_BCI") (pintype "bidirectional"))
      (node (ref "U2") (pin "11") (pinfunction "PA1_11") (pintype "bidirectional"))
    )
    (net (code "26") (name "/KX2") (class "Default")
      (node (ref "U$1") (pin "B4I") (pinfunction "I_B4I") (pintype "bidirectional"))
      (node (ref "U$1") (pin "B5I") (pinfunction "I_B5I") (pintype "bidirectional"))
      (node (ref "U$1") (pin "B6I") (pinfunction "I_B6I") (pintype "bidirectional"))
      (node (ref "U$1") (pin "BMI") (pinfunction "I_BMI") (pintype "bidirectional"))
      (node (ref "U2") (pin "12") (pinfunction "PA2_12") (pintype "bidirectional"))
    )
    (net (code "27") (name "/KX3") (class "Default")
      (node (ref "U$1") (pin "B7I") (pinfunction "I_B7I") (pintype "bidirectional"))
      (node (ref "U$1") (pin "B8I") (pinfunction "I_B8I") (pintype "bidirectional"))
      (node (ref "U$1") (pin "B9I") (pinfunction "I_B9I") (pintype "bidirectional"))
      (node (ref "U$1") (pin "BDI") (pinfunction "I_BDI") (pintype "bidirectional"))
      (node (ref "U2") (pin "13") (pinfunction "PA3_13") (pintype "bidirectional"))
    )
    (net (code "28") (name "/KX4") (class "Default")
      (node (ref "U$1") (pin "B0I") (pinfunction "I_B0I") (pintype "bidirectional"))
      (node (ref "U$1") (pin "BAI") (pinfunction "I_BAI") (pintype "bidirectional"))
      (node (ref "U$1") (pin "BSI") (pinfunction "I_BSI") (pintype "bidirectional"))
      (node (ref "U$1") (pin "BUI") (pinfunction "I_BUI") (pintype "bidirectional"))
      (node (ref "U2") (pin "14") (pinfunction "PA4_14") (pintype "bidirectional"))
    )
    (net (code "29") (name "/KY1") (class "Default")
      (node (ref "U$1") (pin "B1O") (pinfunction "O_B1O") (pintype "bidirectional"))
      (node (ref "U$1") (pin "B4O") (pinfunction "O_B4O") (pintype "bidirectional"))
      (node (ref "U$1") (pin "B7O") (pinfunction "O_B7O") (pintype "bidirectional"))
      (node (ref "U$1") (pin "BAO") (pinfunction "O_BAO") (pintype "bidirectional"))
      (node (ref "U2") (pin "15") (pinfunction "PA5_15") (pintype "bidirectional"))
    )
    (net (code "30") (name "/KY2") (class "Default")
      (node (ref "U$1") (pin "B0O") (pinfunction "O_B0O") (pintype "bidirectional"))
      (node (ref "U$1") (pin "B2O") (pinfunction "O_B2O") (pintype "bidirectional"))
      (node (ref "U$1") (pin "B5O") (pinfunction "O_B5O") (pintype "bidirectional"))
      (node (ref "U$1") (pin "B8O") (pinfunction "O_B8O") (pintype "bidirectional"))
      (node (ref "U2") (pin "16") (pinfunction "PA6_16") (pintype "bidirectional"))
    )
    (net (code "31") (name "/KY3") (class "Default")
      (node (ref "U$1") (pin "B3O") (pinfunction "O_B3O") (pintype "bidirectional"))
      (node (ref "U$1") (pin "B6O") (pinfunction "O_B6O") (pintype "bidirectional"))
      (node (ref "U$1") (pin "B9O") (pinfunction "O_B9O") (pintype "bidirectional"))
      (node (ref "U$1") (pin "BSO") (pinfunction "O_BSO") (pintype "bidirectional"))
      (node (ref "U2") (pin "17") (pinfunction "PA7_17") (pintype "bidirectional"))
    )
    (net (code "32") (name "/KY4") (class "Default")
      (node (ref "U$1") (pin "BCO") (pinfunction "O_BCO") (pintype "bidirectional"))
      (node (ref "U$1") (pin "BDO") (pinfunction "O_BDO") (pintype "bidirectional"))
      (node (ref "U$1") (pin "BMO") (pinfunction "O_BMO") (pintype "bidirectional"))
      (node (ref "U$1") (pin "BUO") (pinfunction "O_BUO") (pintype "bidirectional"))
      (node (ref "U2") (pin "29") (pinfunction "PA8_29") (pintype "bidirectional"))
    )
    (net (code "33") (name "/LED") (class "Default")
      (node (ref "Q4") (pin "1") (pinfunction "G_1") (pintype "passive"))
      (node (ref "U2") (pin "46") (pinfunction "PB9_46") (pintype "bidirectional"))
    )
    (net (code "34") (name "/MISO") (class "Default")
      (node (ref "IC1") (pin "14") (pinfunction "IO25_14") (pintype "bidirectional"))
      (node (ref "U$2") (pin "A2") (pinfunction "MISO_A2") (pintype "bidirectional"))
    )
    (net (code "35") (name "/MOSI") (class "Default")
      (node (ref "IC1") (pin "36") (pinfunction "IO23_36") (pintype "bidirectional"))
      (node (ref "U$1") (pin "P$6") (pinfunction "SI_P$6") (pintype "bidirectional"))
      (node (ref "U$2") (pin "A3") (pinfunction "MOSI_A3") (pintype "bidirectional"))
    )
    (net (code "36") (name "/MOT") (class "Default")
      (node (ref "Q2") (pin "1") (pinfunction "G_1") (pintype "passive"))
      (node (ref "R17") (pin "2") (pinfunction "2_2") (pintype "passive"))
      (node (ref "U2") (pin "42") (pinfunction "PB6_42") (pintype "bidirectional"))
    )
    (net (code "37") (name "/NRST") (class "Default")
      (node (ref "R8") (pin "1") (pinfunction "1_1") (pintype "passive"))
      (node (ref "U$4") (pin "7") (pinfunction "7_7") (pintype "passive"))
      (node (ref "U2") (pin "7") (pinfunction "NRST_7") (pintype "bidirectional"))
    )
    (net (code "38") (name "/RES_LCD") (class "Default")
      (node (ref "IC1") (pin "13") (pinfunction "IO33_13") (pintype "bidirectional"))
      (node (ref "U$1") (pin "P$1") (pinfunction "/RES_P$1") (pintype "bidirectional"))
    )
    (net (code "39") (name "/RST_LORA") (class "Default")
      (node (ref "IC1") (pin "15") (pinfunction "IO26_15") (pintype "bidirectional"))
      (node (ref "U$2") (pin "A6") (pinfunction "RST_A6") (pintype "bidirectional"))
    )
    (net (code "40") (name "/SCLK") (class "Default")
      (node (ref "IC1") (pin "38") (pinfunction "IO19_38") (pintype "bidirectional"))
      (node (ref "U$1") (pin "P$7") (pinfunction "CLK_P$7") (pintype "bidirectional"))
      (node (ref "U$2") (pin "A4") (pinfunction "SCK_A4") (pintype "bidirectional"))
    )
    (net (code "41") (name "/SWCLK") (class "Default")
      (node (ref "U$4") (pin "5") (pinfunction "5_5") (pintype "passive"))
      (node (ref "U2") (pin "37") (pinfunction "PA14_37") (pintype "bidirectional"))
    )
    (net (code "42") (name "/SWDIO") (class "Default")
      (node (ref "U$4") (pin "6") (pinfunction "6_6") (pintype "passive"))
      (node (ref "U2") (pin "34") (pinfunction "PA13_34") (pintype "bidirectional"))
    )
    (net (code "43") (name "/S_RX") (class "Default")
      (node (ref "U$4") (pin "2") (pinfunction "2_2") (pintype "passive"))
      (node (ref "U2") (pin "31") (pinfunction "PA10_31") (pintype "bidirectional"))
    )
    (net (code "44") (name "/S_TX") (class "Default")
      (node (ref "U$4") (pin "3") (pinfunction "3_3") (pintype "passive"))
      (node (ref "U2") (pin "30") (pinfunction "PA9_30") (pintype "bidirectional"))
    )
    (net (code "45") (name "/USB_PRES") (class "Default")
      (node (ref "R14") (pin "1") (pinfunction "1_1") (pintype "passive"))
      (node (ref "R15") (pin "2") (pinfunction "2_2") (pintype "passive"))
      (node (ref "U2") (pin "39") (pinfunction "PB3_39") (pintype "bidirectional"))
    )
    (net (code "46") (name "/VBAT") (class "Default")
      (node (ref "C3") (pin "1") (pinfunction "1_1") (pintype "passive"))
      (node (ref "Q3") (pin "3") (pinfunction "D_3") (pintype "passive"))
      (node (ref "R12") (pin "2") (pinfunction "2_2") (pintype "passive"))
      (node (ref "U$1") (pin "BATT+") (pinfunction "VBATT_BATT+") (pintype "bidirectional"))
      (node (ref "U3") (pin "3") (pinfunction "VBAT_3") (pintype "power_in"))
    )
    (net (code "47") (name "GND") (class "Default")
      (node (ref "ANT1") (pin "GND1") (pinfunction "GND1_GND1") (pintype "bidirectional"))
      (node (ref "ANT1") (pin "GND2") (pinfunction "GND2_GND2") (pintype "bidirectional"))
      (node (ref "C1") (pin "1") (pinfunction "1_1") (pintype "passive"))
      (node (ref "C10") (pin "2") (pinfunction "2_2") (pintype "passive"))
      (node (ref "C11") (pin "2") (pinfunction "2_2") (pintype "passive"))
      (node (ref "C12") (pin "1") (pinfunction "1_1") (pintype "passive"))
      (node (ref "C13") (pin "1") (pinfunction "1_1") (pintype "passive"))
      (node (ref "C14") (pin "2") (pinfunction "2_2") (pintype "passive"))
      (node (ref "C15") (pin "2") (pinfunction "2_2") (pintype "passive"))
      (node (ref "C16") (pin "2") (pinfunction "2_2") (pintype "passive"))
      (node (ref "C18") (pin "-") (pinfunction "-_-") (pintype "passive"))
      (node (ref "C19") (pin "2") (pinfunction "2_2") (pintype "passive"))
      (node (ref "C2") (pin "2") (pinfunction "2_2") (pintype "passive"))
      (node (ref "C20") (pin "2") (pinfunction "2_2") (pintype "passive"))
      (node (ref "C21") (pin "2") (pinfunction "2_2") (pintype "passive"))
      (node (ref "C22") (pin "2") (pinfunction "2_2") (pintype "passive"))
      (node (ref "C23") (pin "-") (pinfunction "-_-") (pintype "passive"))
      (node (ref "C24") (pin "-") (pinfunction "-_-") (pintype "passive"))
      (node (ref "C25") (pin "2") (pinfunction "2_2") (pintype "passive"))
      (node (ref "C3") (pin "2") (pinfunction "2_2") (pintype "passive"))
      (node (ref "C4") (pin "2") (pinfunction "2_2") (pintype "passive"))
      (node (ref "C5") (pin "2") (pinfunction "2_2") (pintype "passive"))
      (node (ref "C6") (pin "2") (pinfunction "2_2") (pintype "passive"))
      (node (ref "C7") (pin "2") (pinfunction "2_2") (pintype "passive"))
      (node (ref "C8") (pin "2") (pinfunction "2_2") (pintype "passive"))
      (node (ref "C9") (pin "2") (pinfunction "2_2") (pintype "passive"))
      (node (ref "IC1") (pin "49") (pinfunction "GND_49") (pintype "bidirectional"))
      (node (ref "J1") (pin "GND") (pinfunction "GND_GND") (pintype "power_in"))
      (node (ref "J1") (pin "MT1") (pinfunction "SHIELD_MT1") (pintype "bidirectional"))
      (node (ref "J1") (pin "MT2") (pinfunction "SHIELD_MT2") (pintype "bidirectional"))
      (node (ref "J1") (pin "P$1") (pinfunction "SHIELD_P$1") (pintype "bidirectional"))
      (node (ref "J1") (pin "P$2") (pinfunction "SHIELD_P$2") (pintype "bidirectional"))
      (node (ref "L1") (pin "2") (pinfunction "2_2") (pintype "passive"))
      (node (ref "Q1") (pin "2") (pinfunction "S_2") (pintype "passive"))
      (node (ref "Q2") (pin "2") (pinfunction "S_2") (pintype "passive"))
      (node (ref "Q4") (pin "2") (pinfunction "S_2") (pintype "passive"))
      (node (ref "R13") (pin "1") (pinfunction "1_1") (pintype "passive"))
      (node (ref "R15") (pin "1") (pinfunction "1_1") (pintype "passive"))
      (node (ref "R17") (pin "1") (pinfunction "1_1") (pintype "passive"))
      (node (ref "R19") (pin "2") (pinfunction "2_2") (pintype "passive"))
      (node (ref "R4") (pin "1") (pinfunction "1_1") (pintype "passive"))
      (node (ref "R5") (pin "1") (pinfunction "1_1") (pintype "passive"))
      (node (ref "R9") (pin "1") (pinfunction "1_1") (pintype "passive"))
      (node (ref "U$1") (pin "BATT-") (pinfunction "BGND_BATT-") (pintype "bidirectional"))
      (node (ref "U$1") (pin "G1") (pinfunction "G1_G1") (pintype "bidirectional"))
      (node (ref "U$1") (pin "G2") (pinfunction "G2_G2") (pintype "bidirectional"))
      (node (ref "U$1") (pin "P$3") (pinfunction "VSS_P$3") (pintype "bidirectional"))
      (node (ref "U$1") (pin "PW2A") (pinfunction "BPI1_PW2A") (pintype "bidirectional"))
      (node (ref "U$1") (pin "PW2B") (pinfunction "BPI2_PW2B") (pintype "bidirectional"))
      (node (ref "U$1") (pin "SPK2") (pinfunction "S+_SPK2") (pintype "bidirectional"))
      (node (ref "U$2") (pin "A1") (pinfunction "GND.1_A1") (pintype "power_in"))
      (node (ref "U$2") (pin "A8") (pinfunction "GND.2_A8") (pintype "power_in"))
      (node (ref "U$2") (pin "B7") (pinfunction "GND.3_B7") (pintype "power_in"))
      (node (ref "U$3") (pin "GND") (pinfunction "GND_GND") (pintype "bidirectional"))
      (node (ref "U$3") (pin "GND@1") (pinfunction "GND_GND@1") (pintype "bidirectional"))
      (node (ref "U$4") (pin "1") (pinfunction "1_1") (pintype "passive"))
      (node (ref "U$4") (pin "M1") (pinfunction "1_M1") (pintype "passive"))
      (node (ref "U$4") (pin "M2") (pinfunction "2_M2") (pintype "passive"))
      (node (ref "U$6") (pin "1") (pinfunction "GND_1") (pintype "bidirectional"))
      (node (ref "U2") (pin "23") (pinfunction "VSS_1_23") (pintype "bidirectional"))
      (node (ref "U2") (pin "35") (pinfunction "VSS_2_35") (pintype "passive"))
      (node (ref "U2") (pin "47") (pinfunction "VSS_3_47") (pintype "passive"))
      (node (ref "U2") (pin "8") (pinfunction "VSSA_8") (pintype "passive"))
      (node (ref "U3") (pin "2") (pinfunction "VSS_2") (pintype "power_in"))
    )
    (net (code "48") (name "Net-(C16-Pad1)") (class "Default")
      (node (ref "C16") (pin "1") (pinfunction "1_1") (pintype "passive"))
      (node (ref "C17") (pin "1") (pinfunction "1_1") (pintype "passive"))
      (node (ref "U$3") (pin "FEED") (pinfunction "FEED_FEED") (pintype "bidirectional"))
    )
    (net (code "49") (name "Net-(D4-PadA)") (class "Default")
      (node (ref "D4") (pin "A") (pinfunction "A_A") (pintype "passive"))
      (node (ref "D5") (pin "A") (pinfunction "A_A") (pintype "passive"))
      (node (ref "D6") (pin "A") (pinfunction "A_A") (pintype "passive"))
      (node (ref "D7") (pin "A") (pinfunction "A_A") (pintype "passive"))
      (node (ref "R7") (pin "1") (pinfunction "1_1") (pintype "passive"))
    )
    (net (code "50") (name "Net-(IC1-LNA_IN)") (class "Default")
      (node (ref "C17") (pin "2") (pinfunction "2_2") (pintype "passive"))
      (node (ref "IC1") (pin "2") (pinfunction "LNA_IN_2") (pintype "bidirectional"))
      (node (ref "L1") (pin "1") (pinfunction "1_1") (pintype "passive"))
    )
    (net (code "51") (name "Net-(J1-PadD+)") (class "Default")
      (node (ref "J1") (pin "D+") (pinfunction "D+_D+") (pintype "bidirectional"))
      (node (ref "R1") (pin "1") (pinfunction "1_1") (pintype "passive"))
    )
    (net (code "52") (name "Net-(J1-PadD-)") (class "Default")
      (node (ref "J1") (pin "D-") (pinfunction "D-_D-") (pintype "bidirectional"))
      (node (ref "R2") (pin "1") (pinfunction "1_1") (pintype "passive"))
    )
    (net (code "53") (name "Net-(Q1-D)") (class "Default")
      (node (ref "D1") (pin "+") (pinfunction "+_+") (pintype "passive"))
      (node (ref "Q1") (pin "3") (pinfunction "D_3") (pintype "passive"))
      (node (ref "U$1") (pin "BUZ1") (pinfunction "B+_BUZ1") (pintype "bidirectional"))
    )
    (net (code "54") (name "Net-(Q1-G)") (class "Default")
      (node (ref "C26") (pin "2") (pinfunction "2_2") (pintype "passive"))
      (node (ref "Q1") (pin "1") (pinfunction "G_1") (pintype "passive"))
      (node (ref "R19") (pin "1") (pinfunction "1_1") (pintype "passive"))
    )
    (net (code "55") (name "Net-(Q2-D)") (class "Default")
      (node (ref "D2") (pin "+") (pinfunction "+_+") (pintype "passive"))
      (node (ref "Q2") (pin "3") (pinfunction "D_3") (pintype "passive"))
      (node (ref "U$1") (pin "MOT1") (pinfunction "-_MOT1") (pintype "bidirectional"))
    )
    (net (code "56") (name "Net-(Q3-S)") (class "Default")
      (node (ref "C23") (pin "+") (pinfunction "+_+") (pintype "passive"))
      (node (ref "C4") (pin "1") (pinfunction "1_1") (pintype "passive"))
      (node (ref "C5") (pin "1") (pinfunction "1_1") (pintype "passive"))
      (node (ref "D3") (pin "-") (pinfunction "-_-") (pintype "passive"))
      (node (ref "Q3") (pin "2") (pinfunction "S_2") (pintype "passive"))
      (node (ref "U$6") (pin "3") (pinfunction "IN_3") (pintype "bidirectional"))
    )
    (net (code "57") (name "Net-(Q4-D)") (class "Default")
      (node (ref "D4") (pin "C") (pinfunction "C_C") (pintype "passive"))
      (node (ref "D5") (pin "C") (pinfunction "C_C") (pintype "passive"))
      (node (ref "D6") (pin "C") (pinfunction "C_C") (pintype "passive"))
      (node (ref "D7") (pin "C") (pinfunction "C_C") (pintype "passive"))
      (node (ref "Q4") (pin "3") (pinfunction "D_3") (pintype "passive"))
    )
    (net (code "58") (name "Net-(TP4-1)") (class "Default")
      (node (ref "TP4") (pin "P$1") (pinfunction "1_P$1") (pintype "bidirectional"))
      (node (ref "U$1") (pin "BTEMP") (pinfunction "BTEMP_BTEMP") (pintype "bidirectional"))
    )
    (net (code "59") (name "Net-(TP5-1)") (class "Default")
      (node (ref "TP5") (pin "P$1") (pinfunction "1_P$1") (pintype "bidirectional"))
      (node (ref "U$1") (pin "B_SI") (pinfunction "BSI_B_SI") (pintype "bidirectional"))
    )
    (net (code "60") (name "Net-(TP6-1)") (class "Default")
      (node (ref "TP6") (pin "P$1") (pinfunction "1_P$1") (pintype "bidirectional"))
      (node (ref "U$1") (pin "SPK1") (pinfunction "-_SPK1") (pintype "bidirectional"))
    )
    (net (code "61") (name "Net-(U$1A-VO)") (class "Default")
      (node (ref "C1") (pin "2") (pinfunction "2_2") (pintype "passive"))
      (node (ref "U$1") (pin "P$2") (pinfunction "VO_P$2") (pintype "bidirectional"))
    )
    (net (code "62") (name "Net-(U$2-ANT)") (class "Default")
      (node (ref "ANT1") (pin "D") (pinfunction "D_D") (pintype "bidirectional"))
      (node (ref "R10") (pin "2") (pinfunction "2_2") (pintype "passive"))
      (node (ref "U$2") (pin "B8") (pinfunction "ANT_B8") (pintype "passive"))
    )
    (net (code "63") (name "Net-(U2-PB0)") (class "Default")
      (node (ref "U$4") (pin "8") (pinfunction "8_8") (pintype "passive"))
      (node (ref "U2") (pin "18") (pinfunction "PB0_18") (pintype "bidirectional"))
    )
    (net (code "64") (name "Net-(U2-PB1)") (class "Default")
      (node (ref "C22") (pin "1") (pinfunction "1_1") (pintype "passive"))
      (node (ref "R12") (pin "1") (pinfunction "1_1") (pintype "passive"))
      (node (ref "R13") (pin "2") (pinfunction "2_2") (pintype "passive"))
      (node (ref "U2") (pin "19") (pinfunction "PB1_19") (pintype "bidirectional"))
    )
    (net (code "65") (name "Net-(U2-PB5)") (class "Default")
      (node (ref "R6") (pin "2") (pinfunction "2_2") (pintype "passive"))
      (node (ref "U2") (pin "41") (pinfunction "PB5_41") (pintype "bidirectional"))
    )
    (net (code "66") (name "Net-(U2-PD0-OSC_IN)") (class "Default")
      (node (ref "C13") (pin "2") (pinfunction "2_2") (pintype "passive"))
      (node (ref "U2") (pin "5") (pinfunction "PD0-OSC_IN_5") (pintype "bidirectional"))
      (node (ref "Y1") (pin "3") (pinfunction "2_3") (pintype "passive"))
    )
    (net (code "67") (name "Net-(U2-PD1-OSC_OUT)") (class "Default")
      (node (ref "C12") (pin "2") (pinfunction "2_2") (pintype "passive"))
      (node (ref "U2") (pin "6") (pinfunction "PD1-OSC_OUT_6") (pintype "bidirectional"))
      (node (ref "Y1") (pin "1") (pinfunction "1_1") (pintype "passive"))
    )
    (net (code "68") (name "Net-(U3-PROG)") (class "Default")
      (node (ref "R4") (pin "2") (pinfunction "2_2") (pintype "passive"))
      (node (ref "U3") (pin "5") (pinfunction "PROG_5") (pintype "input"))
    )
    (net (code "69") (name "Net-(U3-STAT)") (class "Default")
      (node (ref "R16") (pin "2") (pinfunction "2_2") (pintype "passive"))
      (node (ref "U3") (pin "1") (pinfunction "STAT_1") (pintype "output"))
    )
    (net (code "70") (name "unconnected-(IC1-CAP1_NC-Pad48)") (class "Default")
      (node (ref "IC1") (pin "48") (pinfunction "CAP1_NC_48") (pintype "bidirectional"))
    )
    (net (code "71") (name "unconnected-(IC1-CAP2_NC-Pad47)") (class "Default")
      (node (ref "IC1") (pin "47") (pinfunction "CAP2_NC_47") (pintype "bidirectional"))
    )
    (net (code "72") (name "unconnected-(IC1-CMD-Pad30)") (class "Default")
      (node (ref "IC1") (pin "30") (pinfunction "CMD_30") (pintype "bidirectional"))
    )
    (net (code "73") (name "unconnected-(IC1-IO2-Pad22)") (class "Default")
      (node (ref "IC1") (pin "22") (pinfunction "IO2_22") (pintype "bidirectional"))
    )
    (net (code "74") (name "unconnected-(IC1-IO4-Pad24)") (class "Default")
      (node (ref "IC1") (pin "24") (pinfunction "IO4_24") (pintype "bidirectional"))
    )
    (net (code "75") (name "unconnected-(IC1-IO12-Pad18)") (class "Default")
      (node (ref "IC1") (pin "18") (pinfunction "IO12_18") (pintype "bidirectional"))
    )
    (net (code "76") (name "unconnected-(IC1-IO13-Pad20)") (class "Default")
      (node (ref "IC1") (pin "20") (pinfunction "IO13_20") (pintype "bidirectional"))
    )
    (net (code "77") (name "unconnected-(IC1-IO15-Pad21)") (class "Default")
      (node (ref "IC1") (pin "21") (pinfunction "IO15_21") (pintype "bidirectional"))
    )
    (net (code "78") (name "unconnected-(IC1-IO16-Pad25)") (class "Default")
      (node (ref "IC1") (pin "25") (pinfunction "IO16_25") (pintype "bidirectional"))
    )
    (net (code "79") (name "unconnected-(IC1-IO17-Pad27)") (class "Default")
      (node (ref "IC1") (pin "27") (pinfunction "IO17_27") (pintype "bidirectional"))
    )
    (net (code "80") (name "unconnected-(IC1-IO21-Pad42)") (class "Default")
      (node (ref "IC1") (pin "42") (pinfunction "IO21_42") (pintype "bidirectional"))
    )
    (net (code "81") (name "unconnected-(IC1-IO22-Pad39)") (class "Default")
      (node (ref "IC1") (pin "39") (pinfunction "IO22_39") (pintype "bidirectional"))
    )
    (net (code "82") (name "unconnected-(IC1-IO35-Pad11)") (class "Default")
      (node (ref "IC1") (pin "11") (pinfunction "IO35_11") (pintype "bidirectional"))
    )
    (net (code "83") (name "unconnected-(IC1-SD0-Pad32)") (class "Default")
      (node (ref "IC1") (pin "32") (pinfunction "SD0_32") (pintype "bidirectional"))
    )
    (net (code "84") (name "unconnected-(IC1-SD1-Pad33)") (class "Default")
      (node (ref "IC1") (pin "33") (pinfunction "SD1_33") (pintype "bidirectional"))
    )
    (net (code "85") (name "unconnected-(IC1-SD2-Pad28)") (class "Default")
      (node (ref "IC1") (pin "28") (pinfunction "SD2_28") (pintype "bidirectional"))
    )
    (net (code "86") (name "unconnected-(IC1-SD3-Pad29)") (class "Default")
      (node (ref "IC1") (pin "29") (pinfunction "SD3_29") (pintype "bidirectional"))
    )
    (net (code "87") (name "unconnected-(IC1-SLK-Pad31)") (class "Default")
      (node (ref "IC1") (pin "31") (pinfunction "SLK_31") (pintype "bidirectional"))
    )
    (net (code "88") (name "unconnected-(IC1-VDD_SDIO_NC-Pad26)") (class "Default")
      (node (ref "IC1") (pin "26") (pinfunction "VDD_SDIO_NC_26") (pintype "bidirectional"))
    )
    (net (code "89") (name "unconnected-(IC1-XTAL_N_NC-Pad44)") (class "Default")
      (node (ref "IC1") (pin "44") (pinfunction "XTAL_N_NC_44") (pintype "bidirectional"))
    )
    (net (code "90") (name "unconnected-(IC1-XTAL_P_NC-Pad45)") (class "Default")
      (node (ref "IC1") (pin "45") (pinfunction "XTAL_P_NC_45") (pintype "bidirectional"))
    )
    (net (code "91") (name "unconnected-(J1-PadID)") (class "Default")
      (node (ref "J1") (pin "ID") (pinfunction "ID_ID") (pintype "bidirectional"))
    )
    (net (code "92") (name "unconnected-(U$1N---PadANTG)") (class "Default")
      (node (ref "U$1") (pin "ANTG") (pinfunction "-_ANTG") (pintype "bidirectional"))
    )
    (net (code "93") (name "unconnected-(U$1N-ANT-PadANTP)") (class "Default")
      (node (ref "U$1") (pin "ANTP") (pinfunction "ANT_ANTP") (pintype "bidirectional"))
    )
    (net (code "94") (name "unconnected-(U$2-DIO0-PadB3)") (class "Default")
      (node (ref "U$2") (pin "B3") (pinfunction "DIO0_B3") (pintype "bidirectional"))
    )
    (net (code "95") (name "unconnected-(U$2-DIO1-PadB2)") (class "Default")
      (node (ref "U$2") (pin "B2") (pinfunction "DIO1_B2") (pintype "bidirectional"))
    )
    (net (code "96") (name "unconnected-(U$2-DIO2-PadB1)") (class "Default")
      (node (ref "U$2") (pin "B1") (pinfunction "DIO2_B1") (pintype "bidirectional"))
    )
    (net (code "97") (name "unconnected-(U$2-DIO3-PadB6)") (class "Default")
      (node (ref "U$2") (pin "B6") (pinfunction "DIO3_B6") (pintype "bidirectional"))
    )
    (net (code "98") (name "unconnected-(U$2-DIO4-PadB5)") (class "Default")
      (node (ref "U$2") (pin "B5") (pinfunction "DIO4_B5") (pintype "bidirectional"))
    )
    (net (code "99") (name "unconnected-(U$2-DIO5-PadA7)") (class "Default")
      (node (ref "U$2") (pin "A7") (pinfunction "DIO5_A7") (pintype "bidirectional"))
    )
    (net (code "100") (name "unconnected-(U2-PA15-Pad38)") (class "Default")
      (node (ref "U2") (pin "38") (pinfunction "PA15_38") (pintype "bidirectional"))
    )
    (net (code "101") (name "unconnected-(U2-PB8-Pad45)") (class "Default")
      (node (ref "U2") (pin "45") (pinfunction "PB8_45") (pintype "bidirectional"))
    )
    (net (code "102") (name "unconnected-(U2-PB13-Pad26)") (class "Default")
      (node (ref "U2") (pin "26") (pinfunction "PB13_26") (pintype "bidirectional"))
    )
    (net (code "103") (name "unconnected-(U2-PB14-Pad27)") (class "Default")
      (node (ref "U2") (pin "27") (pinfunction "PB14_27") (pintype "bidirectional"))
    )
    (net (code "104") (name "unconnected-(U2-PB15-Pad28)") (class "Default")
      (node (ref "U2") (pin "28") (pinfunction "PB15_28") (pintype "bidirectional"))
    )
    (net (code "105") (name "unconnected-(U2-PC13-TAMPER-RTC-Pad2)") (class "Default")
      (node (ref "U2") (pin "2") (pinfunction "PC13-TAMPER-RTC_2") (pintype "bidirectional"))
    )
    (net (code "106") (name "unconnected-(U2-PC14-OSC32_IN-Pad3)") (class "Default")
      (node (ref "U2") (pin "3") (pinfunction "PC14-OSC32_IN_3") (pintype "bidirectional"))
    )
    (net (code "107") (name "unconnected-(U2-PC15-OSC32_OUT-Pad4)") (class "Default")
      (node (ref "U2") (pin "4") (pinfunction "PC15-OSC32_OUT_4") (pintype "bidirectional"))
    )
  )
)
